# MainBoard_V100_USB_MUX.net
KiCad netlist of a schematic drawn in Altium Designer
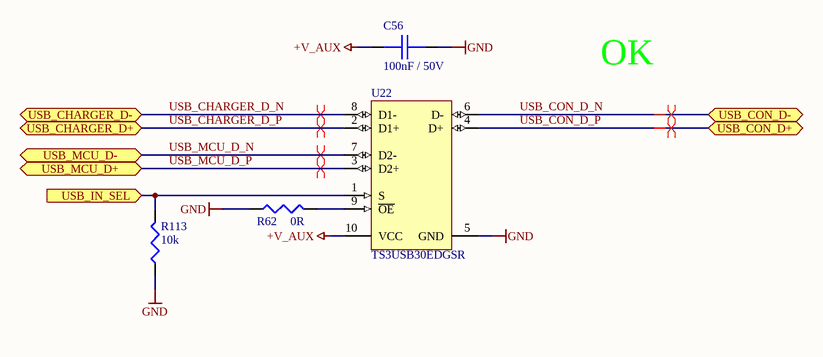
[diagram p0: MainBoard_V100_USB_MUX.SchDoc]

(export (version "E")
  (design (tool "Eeschema 10.0.6"))
  (components
    (comp (ref "C56")
      (value "100nF / 50V")
      (footprint "0805_C")
      (description "100nF 50V X7R")
      (fields (field (name "PART NUMBER") "SMD0805-100nF-50V"))
      (libsource (lib "ALTIUM_DB_LIB") (part "CAP_NONPOL"))
    )
    (comp (ref "R62")
      (value "0R")
      (footprint "0805")
      (description "0R 0805 0.125W 5%")
      (fields (field (name "PART NUMBER") "0 R 5%"))
      (libsource (lib "ALTIUM_DB_LIB") (part "RESISTOR"))
    )
    (comp (ref "R113")
      (value "10k")
      (footprint "0805")
      (description "10k 0805 0.125W 1%")
      (fields (field (name "PART NUMBER") "SMD0805-10k 1%"))
      (libsource (lib "ALTIUM_DB_LIB") (part "RESISTOR"))
    )
    (comp (ref "U22")
      (value "TS3USB30EDGSR")
      (footprint "MSOP-10_P0.5")
      (libsource (lib "ALTIUM_DB_LIB") (part "TS3USB30EDGSR"))
    )
  )
  (nets
    (net (code "1") (name "+V_AUX") (class "Default")
      (node (ref "C56") (pin "2") (pintype "passive"))
      (node (ref "U22") (pin "10") (pinfunction "VCC_10") (pintype "power_in"))
    )
    (net (code "2") (name "/USB_CHARGER_D_N") (class "Default")
      (node (ref "U22") (pin "8") (pinfunction "D1-_8") (pintype "bidirectional"))
    )
    (net (code "3") (name "/USB_CHARGER_D_P") (class "Default")
      (node (ref "U22") (pin "2") (pinfunction "D1+_2") (pintype "bidirectional"))
    )
    (net (code "4") (name "/USB_CON_D_N") (class "Default")
      (node (ref "U22") (pin "6") (pinfunction "D-_6") (pintype "bidirectional"))
    )
    (net (code "5") (name "/USB_CON_D_P") (class "Default")
      (node (ref "U22") (pin "4") (pinfunction "D+_4") (pintype "bidirectional"))
    )
    (net (code "6") (name "/USB_IN_SEL") (class "Default")
      (node (ref "R113") (pin "2") (pintype "passive"))
      (node (ref "U22") (pin "1") (pinfunction "S_1") (pintype "input"))
    )
    (net (code "7") (name "/USB_MCU_D_N") (class "Default")
      (node (ref "U22") (pin "7") (pinfunction "D2-_7") (pintype "bidirectional"))
    )
    (net (code "8") (name "/USB_MCU_D_P") (class "Default")
      (node (ref "U22") (pin "3") (pinfunction "D2+_3") (pintype "bidirectional"))
    )
    (net (code "9") (name "GND") (class "Default")
      (node (ref "C56") (pin "1") (pintype "passive"))
      (node (ref "R113") (pin "1") (pintype "passive"))
      (node (ref "R62") (pin "1") (pintype "passive"))
      (node (ref "U22") (pin "5") (pinfunction "GND_5") (pintype "power_in"))
    )
    (net (code "10") (name "Net-(U22-~{OE})") (class "Default")
      (node (ref "R62") (pin "2") (pintype "passive"))
      (node (ref "U22") (pin "9") (pinfunction "~{OE}_9") (pintype "input"))
    )
  )
)
